# Analyzer_Connector.net
KiCad netlist of a schematic drawn in Altium Designer
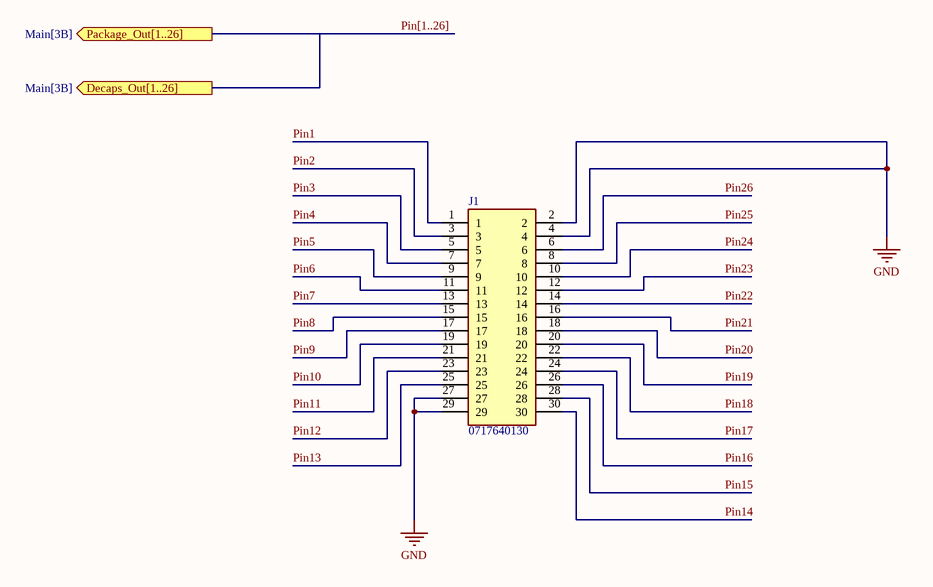
[diagram p0: Analyzer Connector.SchDoc]

(export (version "E")
  (design (tool "Eeschema 10.0.6"))
  (components
    (comp (ref "J1")
      (value "0717640130")
      (footprint "Packaging:HDRRA30W64P254_2X15_3810X229X533P")
      (description "Connector")
      (libsource (lib "*") (part "0717640130"))
    )
  )
  (nets
    (net (code "28") (name "/Pin1") (class "Default")
      (node (ref "J1") (pin "1") (pinfunction "1_1") (pintype "passive"))
    )
    (net (code "29") (name "/Pin2") (class "Default")
      (node (ref "J1") (pin "3") (pinfunction "3_3") (pintype "passive"))
    )
    (net (code "30") (name "/Pin3") (class "Default")
      (node (ref "J1") (pin "5") (pinfunction "5_5") (pintype "passive"))
    )
    (net (code "31") (name "/Pin4") (class "Default")
      (node (ref "J1") (pin "7") (pinfunction "7_7") (pintype "passive"))
    )
    (net (code "32") (name "/Pin5") (class "Default")
      (node (ref "J1") (pin "9") (pinfunction "9_9") (pintype "passive"))
    )
    (net (code "33") (name "/Pin6") (class "Default")
      (node (ref "J1") (pin "11") (pinfunction "11_11") (pintype "passive"))
    )
    (net (code "34") (name "/Pin7") (class "Default")
      (node (ref "J1") (pin "13") (pinfunction "13_13") (pintype "passive"))
    )
    (net (code "35") (name "/Pin8") (class "Default")
      (node (ref "J1") (pin "15") (pinfunction "15_15") (pintype "passive"))
    )
    (net (code "36") (name "/Pin9") (class "Default")
      (node (ref "J1") (pin "17") (pinfunction "17_17") (pintype "passive"))
    )
    (net (code "37") (name "/Pin10") (class "Default")
      (node (ref "J1") (pin "19") (pinfunction "19_19") (pintype "passive"))
    )
    (net (code "38") (name "/Pin11") (class "Default")
      (node (ref "J1") (pin "21") (pinfunction "21_21") (pintype "passive"))
    )
    (net (code "39") (name "/Pin12") (class "Default")
      (node (ref "J1") (pin "23") (pinfunction "23_23") (pintype "passive"))
    )
    (net (code "40") (name "/Pin13") (class "Default")
      (node (ref "J1") (pin "25") (pinfunction "25_25") (pintype "passive"))
    )
    (net (code "41") (name "/Pin14") (class "Default")
      (node (ref "J1") (pin "30") (pinfunction "30_30") (pintype "passive"))
    )
    (net (code "42") (name "/Pin15") (class "Default")
      (node (ref "J1") (pin "28") (pinfunction "28_28") (pintype "passive"))
    )
    (net (code "43") (name "/Pin16") (class "Default")
      (node (ref "J1") (pin "26") (pinfunction "26_26") (pintype "passive"))
    )
    (net (code "44") (name "/Pin17") (class "Default")
      (node (ref "J1") (pin "24") (pinfunction "24_24") (pintype "passive"))
    )
    (net (code "45") (name "/Pin18") (class "Default")
      (node (ref "J1") (pin "22") (pinfunction "22_22") (pintype "passive"))
    )
    (net (code "46") (name "/Pin19") (class "Default")
      (node (ref "J1") (pin "20") (pinfunction "20_20") (pintype "passive"))
    )
    (net (code "47") (name "/Pin20") (class "Default")
      (node (ref "J1") (pin "18") (pinfunction "18_18") (pintype "passive"))
    )
    (net (code "48") (name "/Pin21") (class "Default")
      (node (ref "J1") (pin "16") (pinfunction "16_16") (pintype "passive"))
    )
    (net (code "49") (name "/Pin22") (class "Default")
      (node (ref "J1") (pin "14") (pinfunction "14_14") (pintype "passive"))
    )
    (net (code "50") (name "/Pin23") (class "Default")
      (node (ref "J1") (pin "12") (pinfunction "12_12") (pintype "passive"))
    )
    (net (code "51") (name "/Pin24") (class "Default")
      (node (ref "J1") (pin "10") (pinfunction "10_10") (pintype "passive"))
    )
    (net (code "52") (name "/Pin25") (class "Default")
      (node (ref "J1") (pin "8") (pinfunction "8_8") (pintype "passive"))
    )
    (net (code "53") (name "/Pin26") (class "Default")
      (node (ref "J1") (pin "6") (pinfunction "6_6") (pintype "passive"))
    )
    (net (code "55") (name "GND") (class "Default")
      (node (ref "J1") (pin "2") (pinfunction "2_2") (pintype "passive"))
      (node (ref "J1") (pin "27") (pinfunction "27_27") (pintype "passive"))
      (node (ref "J1") (pin "29") (pinfunction "29_29") (pintype "passive"))
      (node (ref "J1") (pin "4") (pinfunction "4_4") (pintype "passive"))
    )
  )
)
